# CF_ADC_filter.net
KiCad netlist of a schematic drawn in Altium Designer
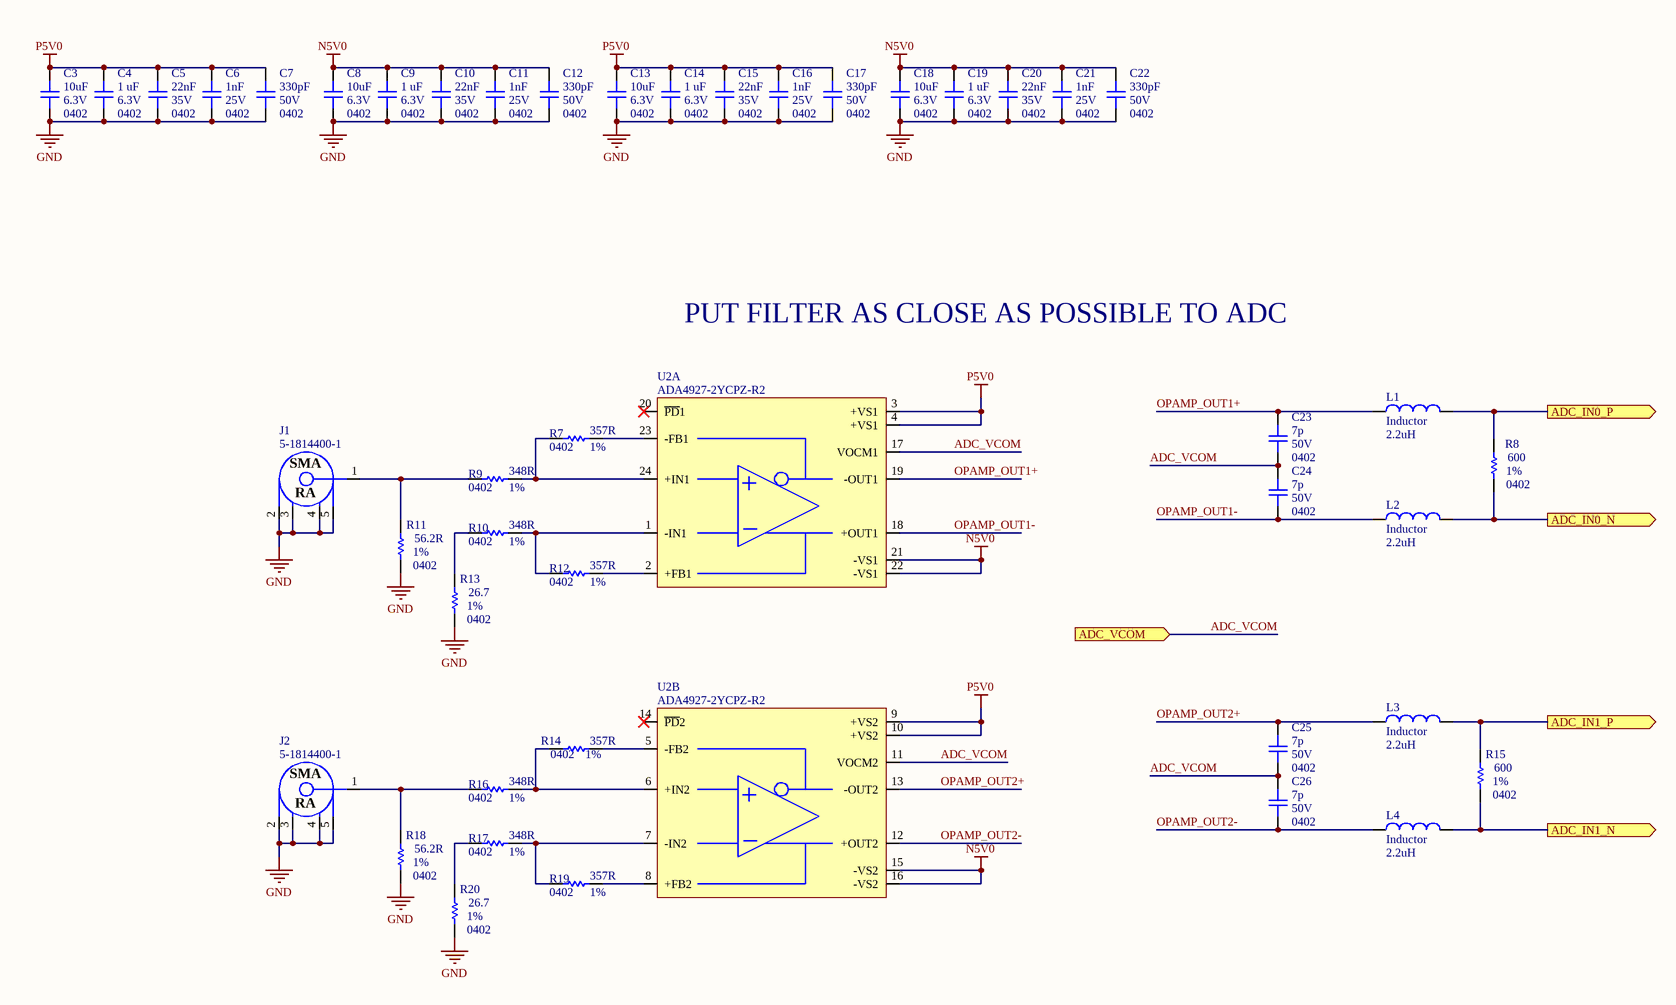
[diagram p0: CF_ADC_filter.SchDoc]

(export (version "E")
  (design (tool "Eeschema 10.0.6"))
  (components
    (comp (ref "C3")
      (value "10uF")
      (footprint "CAP_0402")
      (description "CAP - 0402")
      (fields
        (field (name "VOLTAGE") "6.3V")
        (field (name "PACKAGE") "0402")
        (field (name "CREATEDBY") "Jonathan Bouchard")
      )
      (libsource (lib "S7CAS_Lib2019_REV1_00") (part "CAP - 0402"))
    )
    (comp (ref "C4")
      (value "1 uF")
      (footprint "CAP_0402")
      (description "CAP - 0402")
      (fields
        (field (name "VOLTAGE") "6.3V")
        (field (name "PACKAGE") "0402")
        (field (name "CREATEDBY") "Jonathan Bouchard")
      )
      (libsource (lib "S7CAS_Lib2019_REV1_00") (part "CAP - 0402"))
    )
    (comp (ref "C5")
      (value "22nF")
      (footprint "CAP_0402")
      (description "CAP - 0402")
      (fields
        (field (name "VOLTAGE") "35V")
        (field (name "PACKAGE") "0402")
        (field (name "CREATEDBY") "Jonathan Bouchard")
      )
      (libsource (lib "S7CAS_Lib2019_REV1_00") (part "CAP - 0402"))
    )
    (comp (ref "C6")
      (value "1nF")
      (footprint "CAP_0402")
      (description "CAP - 0402")
      (fields
        (field (name "VOLTAGE") "25V")
        (field (name "PACKAGE") "0402")
        (field (name "CREATEDBY") "Jonathan Bouchard")
      )
      (libsource (lib "S7CAS_Lib2019_REV1_00") (part "CAP - 0402"))
    )
    (comp (ref "C7")
      (value "330pF")
      (footprint "CAP_0402")
      (description "CAP - 0402")
      (fields
        (field (name "VOLTAGE") "50V")
        (field (name "PACKAGE") "0402")
        (field (name "CREATEDBY") "Jonathan Bouchard")
      )
      (libsource (lib "S7CAS_Lib2019_REV1_00") (part "CAP - 0402"))
    )
    (comp (ref "C8")
      (value "10uF")
      (footprint "CAP_0402")
      (description "CAP - 0402")
      (fields
        (field (name "VOLTAGE") "6.3V")
        (field (name "PACKAGE") "0402")
        (field (name "CREATEDBY") "Jonathan Bouchard")
      )
      (libsource (lib "S7CAS_Lib2019_REV1_00") (part "CAP - 0402"))
    )
    (comp (ref "C9")
      (value "1 uF")
      (footprint "CAP_0402")
      (description "CAP - 0402")
      (fields
        (field (name "VOLTAGE") "6.3V")
        (field (name "PACKAGE") "0402")
        (field (name "CREATEDBY") "Jonathan Bouchard")
      )
      (libsource (lib "S7CAS_Lib2019_REV1_00") (part "CAP - 0402"))
    )
    (comp (ref "C10")
      (value "22nF")
      (footprint "CAP_0402")
      (description "CAP - 0402")
      (fields
        (field (name "VOLTAGE") "35V")
        (field (name "PACKAGE") "0402")
        (field (name "CREATEDBY") "Jonathan Bouchard")
      )
      (libsource (lib "S7CAS_Lib2019_REV1_00") (part "CAP - 0402"))
    )
    (comp (ref "C11")
      (value "1nF")
      (footprint "CAP_0402")
      (description "CAP - 0402")
      (fields
        (field (name "VOLTAGE") "25V")
        (field (name "PACKAGE") "0402")
        (field (name "CREATEDBY") "Jonathan Bouchard")
      )
      (libsource (lib "S7CAS_Lib2019_REV1_00") (part "CAP - 0402"))
    )
    (comp (ref "C12")
      (value "330pF")
      (footprint "CAP_0402")
      (description "CAP - 0402")
      (fields
        (field (name "VOLTAGE") "50V")
        (field (name "PACKAGE") "0402")
        (field (name "CREATEDBY") "Jonathan Bouchard")
      )
      (libsource (lib "S7CAS_Lib2019_REV1_00") (part "CAP - 0402"))
    )
    (comp (ref "C13")
      (value "10uF")
      (footprint "CAP_0402")
      (description "CAP - 0402")
      (fields
        (field (name "VOLTAGE") "6.3V")
        (field (name "PACKAGE") "0402")
        (field (name "CREATEDBY") "Jonathan Bouchard")
      )
      (libsource (lib "S7CAS_Lib2019_REV1_00") (part "CAP - 0402"))
    )
    (comp (ref "C14")
      (value "1 uF")
      (footprint "CAP_0402")
      (description "CAP - 0402")
      (fields
        (field (name "VOLTAGE") "6.3V")
        (field (name "PACKAGE") "0402")
        (field (name "CREATEDBY") "Jonathan Bouchard")
      )
      (libsource (lib "S7CAS_Lib2019_REV1_00") (part "CAP - 0402"))
    )
    (comp (ref "C15")
      (value "22nF")
      (footprint "CAP_0402")
      (description "CAP - 0402")
      (fields
        (field (name "VOLTAGE") "35V")
        (field (name "PACKAGE") "0402")
        (field (name "CREATEDBY") "Jonathan Bouchard")
      )
      (libsource (lib "S7CAS_Lib2019_REV1_00") (part "CAP - 0402"))
    )
    (comp (ref "C16")
      (value "1nF")
      (footprint "CAP_0402")
      (description "CAP - 0402")
      (fields
        (field (name "VOLTAGE") "25V")
        (field (name "PACKAGE") "0402")
        (field (name "CREATEDBY") "Jonathan Bouchard")
      )
      (libsource (lib "S7CAS_Lib2019_REV1_00") (part "CAP - 0402"))
    )
    (comp (ref "C17")
      (value "330pF")
      (footprint "CAP_0402")
      (description "CAP - 0402")
      (fields
        (field (name "VOLTAGE") "50V")
        (field (name "PACKAGE") "0402")
        (field (name "CREATEDBY") "Jonathan Bouchard")
      )
      (libsource (lib "S7CAS_Lib2019_REV1_00") (part "CAP - 0402"))
    )
    (comp (ref "C18")
      (value "10uF")
      (footprint "CAP_0402")
      (description "CAP - 0402")
      (fields
        (field (name "VOLTAGE") "6.3V")
        (field (name "PACKAGE") "0402")
        (field (name "CREATEDBY") "Jonathan Bouchard")
      )
      (libsource (lib "S7CAS_Lib2019_REV1_00") (part "CAP - 0402"))
    )
    (comp (ref "C19")
      (value "1 uF")
      (footprint "CAP_0402")
      (description "CAP - 0402")
      (fields
        (field (name "VOLTAGE") "6.3V")
        (field (name "PACKAGE") "0402")
        (field (name "CREATEDBY") "Jonathan Bouchard")
      )
      (libsource (lib "S7CAS_Lib2019_REV1_00") (part "CAP - 0402"))
    )
    (comp (ref "C20")
      (value "22nF")
      (footprint "CAP_0402")
      (description "CAP - 0402")
      (fields
        (field (name "VOLTAGE") "35V")
        (field (name "PACKAGE") "0402")
        (field (name "CREATEDBY") "Jonathan Bouchard")
      )
      (libsource (lib "S7CAS_Lib2019_REV1_00") (part "CAP - 0402"))
    )
    (comp (ref "C21")
      (value "1nF")
      (footprint "CAP_0402")
      (description "CAP - 0402")
      (fields
        (field (name "VOLTAGE") "25V")
        (field (name "PACKAGE") "0402")
        (field (name "CREATEDBY") "Jonathan Bouchard")
      )
      (libsource (lib "S7CAS_Lib2019_REV1_00") (part "CAP - 0402"))
    )
    (comp (ref "C22")
      (value "330pF")
      (footprint "CAP_0402")
      (description "CAP - 0402")
      (fields
        (field (name "VOLTAGE") "50V")
        (field (name "PACKAGE") "0402")
        (field (name "CREATEDBY") "Jonathan Bouchard")
      )
      (libsource (lib "S7CAS_Lib2019_REV1_00") (part "CAP - 0402"))
    )
    (comp (ref "C23")
      (value "7p")
      (footprint "CAP_0402")
      (description "CAP - 0402")
      (fields
        (field (name "VOLTAGE") "50V")
        (field (name "PACKAGE") "0402")
        (field (name "CREATEDBY") "Jonathan Bouchard")
      )
      (libsource (lib "S7CAS_Lib2019_REV1_00") (part "CAP - 0402"))
    )
    (comp (ref "C24")
      (value "7p")
      (footprint "CAP_0402")
      (description "CAP - 0402")
      (fields
        (field (name "VOLTAGE") "50V")
        (field (name "PACKAGE") "0402")
        (field (name "CREATEDBY") "Jonathan Bouchard")
      )
      (libsource (lib "S7CAS_Lib2019_REV1_00") (part "CAP - 0402"))
    )
    (comp (ref "C25")
      (value "7p")
      (footprint "CAP_0402")
      (description "CAP - 0402")
      (fields
        (field (name "VOLTAGE") "50V")
        (field (name "PACKAGE") "0402")
        (field (name "CREATEDBY") "Jonathan Bouchard")
      )
      (libsource (lib "S7CAS_Lib2019_REV1_00") (part "CAP - 0402"))
    )
    (comp (ref "C26")
      (value "7p")
      (footprint "CAP_0402")
      (description "CAP - 0402")
      (fields
        (field (name "VOLTAGE") "50V")
        (field (name "PACKAGE") "0402")
        (field (name "CREATEDBY") "Jonathan Bouchard")
      )
      (libsource (lib "S7CAS_Lib2019_REV1_00") (part "CAP - 0402"))
    )
    (comp (ref "J1")
      (value "5-1814400-1")
      (footprint "CONN_SMA_5-1814400-1")
      (description "CONN -  SMA JACK R/A 50 OHM - TH")
      (fields
        (field (name "MFG") "TE Connectivity AMP Connectors")
        (field (name "CREATEDBY") "Jonathan Bouchard")
      )
      (libsource (lib "S7CAS_Lib2019_REV1_00") (part "CONN_SMA_5-1814400-1"))
    )
    (comp (ref "J2")
      (value "5-1814400-1")
      (footprint "CONN_SMA_5-1814400-1")
      (description "CONN -  SMA JACK R/A 50 OHM - TH")
      (fields
        (field (name "MFG") "TE Connectivity AMP Connectors")
        (field (name "CREATEDBY") "Jonathan Bouchard")
      )
      (libsource (lib "S7CAS_Lib2019_REV1_00") (part "CONN_SMA_5-1814400-1"))
    )
    (comp (ref "L1")
      (value "Inductor")
      (footprint "0402-A")
      (fields (field (name "ALTIUM_VALUE") "2.2uH") (field (name "PUBLISHER") "Altium Limited"))
      (libsource (lib "Miscellaneous Devices") (part "Inductor"))
    )
    (comp (ref "L2")
      (value "Inductor")
      (footprint "0402-A")
      (fields (field (name "ALTIUM_VALUE") "2.2uH") (field (name "PUBLISHER") "Altium Limited"))
      (libsource (lib "Miscellaneous Devices") (part "Inductor"))
    )
    (comp (ref "L3")
      (value "Inductor")
      (footprint "0402-A")
      (fields (field (name "ALTIUM_VALUE") "2.2uH") (field (name "PUBLISHER") "Altium Limited"))
      (libsource (lib "Miscellaneous Devices") (part "Inductor"))
    )
    (comp (ref "L4")
      (value "Inductor")
      (footprint "0402-A")
      (fields (field (name "ALTIUM_VALUE") "2.2uH") (field (name "PUBLISHER") "Altium Limited"))
      (libsource (lib "Miscellaneous Devices") (part "Inductor"))
    )
    (comp (ref "R7")
      (value "357R")
      (footprint "RES_0402")
      (description "RES - 0402")
      (fields
        (field (name "VOLTAGE") "50V")
        (field (name "POWER") "1/16W")
        (field (name "PACKAGE") "0402")
        (field (name "PRECISION") "1%")
        (field (name "CREATEDBY") "Jonathan Bouchard")
      )
      (libsource (lib "S7CAS_Lib2019_REV1_00") (part "RES - 0402"))
    )
    (comp (ref "R8")
      (value "600")
      (footprint "RES_0402")
      (description "RES - 0402")
      (fields
        (field (name "VOLTAGE") "50V")
        (field (name "POWER") "1/16W")
        (field (name "PACKAGE") "0402")
        (field (name "PRECISION") "1%")
        (field (name "CREATEDBY") "Jonathan Bouchard")
      )
      (libsource (lib "S7CAS_Lib2019_REV1_00") (part "RES - 0402"))
    )
    (comp (ref "R9")
      (value "348R")
      (footprint "RES_0402")
      (description "RES - 0402")
      (fields
        (field (name "VOLTAGE") "50V")
        (field (name "POWER") "1/16W")
        (field (name "PACKAGE") "0402")
        (field (name "PRECISION") "1%")
        (field (name "CREATEDBY") "Jonathan Bouchard")
      )
      (libsource (lib "S7CAS_Lib2019_REV1_00") (part "RES - 0402"))
    )
    (comp (ref "R10")
      (value "348R")
      (footprint "RES_0402")
      (description "RES - 0402")
      (fields
        (field (name "VOLTAGE") "50V")
        (field (name "POWER") "1/16W")
        (field (name "PACKAGE") "0402")
        (field (name "PRECISION") "1%")
        (field (name "CREATEDBY") "Jonathan Bouchard")
      )
      (libsource (lib "S7CAS_Lib2019_REV1_00") (part "RES - 0402"))
    )
    (comp (ref "R11")
      (value "56.2R")
      (footprint "RES_0402")
      (description "RES - 0402")
      (fields
        (field (name "VOLTAGE") "50V")
        (field (name "POWER") "1/16W")
        (field (name "PACKAGE") "0402")
        (field (name "PRECISION") "1%")
        (field (name "CREATEDBY") "Jonathan Bouchard")
      )
      (libsource (lib "S7CAS_Lib2019_REV1_00") (part "RES - 0402"))
    )
    (comp (ref "R12")
      (value "357R")
      (footprint "RES_0402")
      (description "RES - 0402")
      (fields
        (field (name "VOLTAGE") "50V")
        (field (name "POWER") "1/16W")
        (field (name "PACKAGE") "0402")
        (field (name "PRECISION") "1%")
        (field (name "CREATEDBY") "Jonathan Bouchard")
      )
      (libsource (lib "S7CAS_Lib2019_REV1_00") (part "RES - 0402"))
    )
    (comp (ref "R13")
      (value "26.7")
      (footprint "RES_0402")
      (description "RES - 0402")
      (fields
        (field (name "VOLTAGE") "50V")
        (field (name "POWER") "1/16W")
        (field (name "PACKAGE") "0402")
        (field (name "PRECISION") "1%")
        (field (name "CREATEDBY") "Jonathan Bouchard")
      )
      (libsource (lib "S7CAS_Lib2019_REV1_00") (part "RES - 0402"))
    )
    (comp (ref "R14")
      (value "357R")
      (footprint "RES_0402")
      (description "RES - 0402")
      (fields
        (field (name "VOLTAGE") "50V")
        (field (name "POWER") "1/16W")
        (field (name "PACKAGE") "0402")
        (field (name "PRECISION") "1%")
        (field (name "CREATEDBY") "Jonathan Bouchard")
      )
      (libsource (lib "S7CAS_Lib2019_REV1_00") (part "RES - 0402"))
    )
    (comp (ref "R15")
      (value "600")
      (footprint "RES_0402")
      (description "RES - 0402")
      (fields
        (field (name "VOLTAGE") "50V")
        (field (name "POWER") "1/16W")
        (field (name "PACKAGE") "0402")
        (field (name "PRECISION") "1%")
        (field (name "CREATEDBY") "Jonathan Bouchard")
      )
      (libsource (lib "S7CAS_Lib2019_REV1_00") (part "RES - 0402"))
    )
    (comp (ref "R16")
      (value "348R")
      (footprint "RES_0402")
      (description "RES - 0402")
      (fields
        (field (name "VOLTAGE") "50V")
        (field (name "POWER") "1/16W")
        (field (name "PACKAGE") "0402")
        (field (name "PRECISION") "1%")
        (field (name "CREATEDBY") "Jonathan Bouchard")
      )
      (libsource (lib "S7CAS_Lib2019_REV1_00") (part "RES - 0402"))
    )
    (comp (ref "R17")
      (value "348R")
      (footprint "RES_0402")
      (description "RES - 0402")
      (fields
        (field (name "VOLTAGE") "50V")
        (field (name "POWER") "1/16W")
        (field (name "PACKAGE") "0402")
        (field (name "PRECISION") "1%")
        (field (name "CREATEDBY") "Jonathan Bouchard")
      )
      (libsource (lib "S7CAS_Lib2019_REV1_00") (part "RES - 0402"))
    )
    (comp (ref "R18")
      (value "56.2R")
      (footprint "RES_0402")
      (description "RES - 0402")
      (fields
        (field (name "VOLTAGE") "50V")
        (field (name "POWER") "1/16W")
        (field (name "PACKAGE") "0402")
        (field (name "PRECISION") "1%")
        (field (name "CREATEDBY") "Jonathan Bouchard")
      )
      (libsource (lib "S7CAS_Lib2019_REV1_00") (part "RES - 0402"))
    )
    (comp (ref "R19")
      (value "357R")
      (footprint "RES_0402")
      (description "RES - 0402")
      (fields
        (field (name "VOLTAGE") "50V")
        (field (name "POWER") "1/16W")
        (field (name "PACKAGE") "0402")
        (field (name "PRECISION") "1%")
        (field (name "CREATEDBY") "Jonathan Bouchard")
      )
      (libsource (lib "S7CAS_Lib2019_REV1_00") (part "RES - 0402"))
    )
    (comp (ref "R20")
      (value "26.7")
      (footprint "RES_0402")
      (description "RES - 0402")
      (fields
        (field (name "VOLTAGE") "50V")
        (field (name "POWER") "1/16W")
        (field (name "PACKAGE") "0402")
        (field (name "PRECISION") "1%")
        (field (name "CREATEDBY") "Jonathan Bouchard")
      )
      (libsource (lib "S7CAS_Lib2019_REV1_00") (part "RES - 0402"))
    )
    (comp (ref "U2")
      (value "ADA4927-2YCPZ-R2")
      (footprint "OPAMP_ADA4927-2YCPZ-R2")
      (description "OPAMP - CFA 2.3GHZ - QFN-24")
      (fields
        (field (name "VOLTAGE") "4.5 V ~ 11 V, ±2.25 V ~ 5.5 V")
        (field (name "MFG") "Analog Devices")
        (field (name "CREATEDBY") "Jonathan Bouchard")
      )
      (libsource (lib "S7CAS_Lib2019_REV1_00") (part "OPAMP_ADA4927-2YCPZ-R2"))
    )
  )
  (nets
    (net (code "1") (name "/ADC_IN0_N") (class "Default")
      (node (ref "L2") (pin "2") (pinfunction "2_2") (pintype "passive"))
      (node (ref "R8") (pin "1") (pinfunction "1_1") (pintype "passive"))
    )
    (net (code "2") (name "/ADC_IN0_P") (class "Default")
      (node (ref "L1") (pin "2") (pinfunction "2_2") (pintype "passive"))
      (node (ref "R8") (pin "2") (pinfunction "2_2") (pintype "passive"))
    )
    (net (code "3") (name "/ADC_IN1_N") (class "Default")
      (node (ref "L4") (pin "2") (pinfunction "2_2") (pintype "passive"))
      (node (ref "R15") (pin "1") (pinfunction "1_1") (pintype "passive"))
    )
    (net (code "4") (name "/ADC_IN1_P") (class "Default")
      (node (ref "L3") (pin "2") (pinfunction "2_2") (pintype "passive"))
      (node (ref "R15") (pin "2") (pinfunction "2_2") (pintype "passive"))
    )
    (net (code "5") (name "/ADC_VCOM") (class "Default")
      (node (ref "C23") (pin "1") (pinfunction "1_1") (pintype "passive"))
      (node (ref "C24") (pin "2") (pinfunction "2_2") (pintype "passive"))
      (node (ref "C25") (pin "1") (pinfunction "1_1") (pintype "passive"))
      (node (ref "C26") (pin "2") (pinfunction "2_2") (pintype "passive"))
      (node (ref "U2") (pin "11") (pinfunction "VOCM2_11") (pintype "passive"))
      (node (ref "U2") (pin "17") (pinfunction "VOCM1_17") (pintype "passive"))
    )
    (net (code "6") (name "/OPAMP_OUT1+") (class "Default")
      (node (ref "C23") (pin "2") (pinfunction "2_2") (pintype "passive"))
      (node (ref "L1") (pin "1") (pinfunction "1_1") (pintype "passive"))
      (node (ref "U2") (pin "19") (pinfunction "-OUT1_19") (pintype "passive"))
    )
    (net (code "7") (name "/OPAMP_OUT1-") (class "Default")
      (node (ref "C24") (pin "1") (pinfunction "1_1") (pintype "passive"))
      (node (ref "L2") (pin "1") (pinfunction "1_1") (pintype "passive"))
      (node (ref "U2") (pin "18") (pinfunction "+OUT1_18") (pintype "passive"))
    )
    (net (code "8") (name "/OPAMP_OUT2+") (class "Default")
      (node (ref "C25") (pin "2") (pinfunction "2_2") (pintype "passive"))
      (node (ref "L3") (pin "1") (pinfunction "1_1") (pintype "passive"))
      (node (ref "U2") (pin "13") (pinfunction "-OUT2_13") (pintype "passive"))
    )
    (net (code "9") (name "/OPAMP_OUT2-") (class "Default")
      (node (ref "C26") (pin "1") (pinfunction "1_1") (pintype "passive"))
      (node (ref "L4") (pin "1") (pinfunction "1_1") (pintype "passive"))
      (node (ref "U2") (pin "12") (pinfunction "+OUT2_12") (pintype "passive"))
    )
    (net (code "10") (name "GND") (class "Default")
      (node (ref "C10") (pin "1") (pinfunction "1_1") (pintype "passive"))
      (node (ref "C11") (pin "1") (pinfunction "1_1") (pintype "passive"))
      (node (ref "C12") (pin "1") (pinfunction "1_1") (pintype "passive"))
      (node (ref "C13") (pin "1") (pinfunction "1_1") (pintype "passive"))
      (node (ref "C14") (pin "1") (pinfunction "1_1") (pintype "passive"))
      (node (ref "C15") (pin "1") (pinfunction "1_1") (pintype "passive"))
      (node (ref "C16") (pin "1") (pinfunction "1_1") (pintype "passive"))
      (node (ref "C17") (pin "1") (pinfunction "1_1") (pintype "passive"))
      (node (ref "C18") (pin "1") (pinfunction "1_1") (pintype "passive"))
      (node (ref "C19") (pin "1") (pinfunction "1_1") (pintype "passive"))
      (node (ref "C20") (pin "1") (pinfunction "1_1") (pintype "passive"))
      (node (ref "C21") (pin "1") (pinfunction "1_1") (pintype "passive"))
      (node (ref "C22") (pin "1") (pinfunction "1_1") (pintype "passive"))
      (node (ref "C3") (pin "1") (pinfunction "1_1") (pintype "passive"))
      (node (ref "C4") (pin "1") (pinfunction "1_1") (pintype "passive"))
      (node (ref "C5") (pin "1") (pinfunction "1_1") (pintype "passive"))
      (node (ref "C6") (pin "1") (pinfunction "1_1") (pintype "passive"))
      (node (ref "C7") (pin "1") (pinfunction "1_1") (pintype "passive"))
      (node (ref "C8") (pin "1") (pinfunction "1_1") (pintype "passive"))
      (node (ref "C9") (pin "1") (pinfunction "1_1") (pintype "passive"))
      (node (ref "J1") (pin "2") (pinfunction "2_2") (pintype "passive"))
      (node (ref "J1") (pin "3") (pinfunction "3_3") (pintype "passive"))
      (node (ref "J1") (pin "4") (pinfunction "4_4") (pintype "passive"))
      (node (ref "J1") (pin "5") (pinfunction "5_5") (pintype "passive"))
      (node (ref "J2") (pin "2") (pinfunction "2_2") (pintype "passive"))
      (node (ref "J2") (pin "3") (pinfunction "3_3") (pintype "passive"))
      (node (ref "J2") (pin "4") (pinfunction "4_4") (pintype "passive"))
      (node (ref "J2") (pin "5") (pinfunction "5_5") (pintype "passive"))
      (node (ref "R11") (pin "1") (pinfunction "1_1") (pintype "passive"))
      (node (ref "R13") (pin "1") (pinfunction "1_1") (pintype "passive"))
      (node (ref "R18") (pin "1") (pinfunction "1_1") (pintype "passive"))
      (node (ref "R20") (pin "1") (pinfunction "1_1") (pintype "passive"))
    )
    (net (code "11") (name "N5V0") (class "Default")
      (node (ref "C10") (pin "2") (pinfunction "2_2") (pintype "passive"))
      (node (ref "C11") (pin "2") (pinfunction "2_2") (pintype "passive"))
      (node (ref "C12") (pin "2") (pinfunction "2_2") (pintype "passive"))
      (node (ref "C18") (pin "2") (pinfunction "2_2") (pintype "passive"))
      (node (ref "C19") (pin "2") (pinfunction "2_2") (pintype "passive"))
      (node (ref "C20") (pin "2") (pinfunction "2_2") (pintype "passive"))
      (node (ref "C21") (pin "2") (pinfunction "2_2") (pintype "passive"))
      (node (ref "C22") (pin "2") (pinfunction "2_2") (pintype "passive"))
      (node (ref "C8") (pin "2") (pinfunction "2_2") (pintype "passive"))
      (node (ref "C9") (pin "2") (pinfunction "2_2") (pintype "passive"))
      (node (ref "U2") (pin "15") (pinfunction "-VS2_15") (pintype "passive"))
      (node (ref "U2") (pin "16") (pinfunction "-VS2_16") (pintype "passive"))
      (node (ref "U2") (pin "21") (pinfunction "-VS1_21") (pintype "passive"))
      (node (ref "U2") (pin "22") (pinfunction "-VS1_22") (pintype "passive"))
    )
    (net (code "12") (name "Net-(J1-Pad1)") (class "Default")
      (node (ref "J1") (pin "1") (pinfunction "1_1") (pintype "passive"))
      (node (ref "R11") (pin "2") (pinfunction "2_2") (pintype "passive"))
      (node (ref "R9") (pin "2") (pinfunction "2_2") (pintype "passive"))
    )
    (net (code "13") (name "Net-(J2-Pad1)") (class "Default")
      (node (ref "J2") (pin "1") (pinfunction "1_1") (pintype "passive"))
      (node (ref "R16") (pin "2") (pinfunction "2_2") (pintype "passive"))
      (node (ref "R18") (pin "2") (pinfunction "2_2") (pintype "passive"))
    )
    (net (code "14") (name "Net-(R10-Pad2)") (class "Default")
      (node (ref "R10") (pin "2") (pinfunction "2_2") (pintype "passive"))
      (node (ref "R13") (pin "2") (pinfunction "2_2") (pintype "passive"))
    )
    (net (code "15") (name "Net-(R17-Pad2)") (class "Default")
      (node (ref "R17") (pin "2") (pinfunction "2_2") (pintype "passive"))
      (node (ref "R20") (pin "2") (pinfunction "2_2") (pintype "passive"))
    )
    (net (code "16") (name "Net-(U2A-+FB1)") (class "Default")
      (node (ref "R12") (pin "1") (pinfunction "1_1") (pintype "passive"))
      (node (ref "U2") (pin "2") (pinfunction "+FB1_2") (pintype "passive"))
    )
    (net (code "17") (name "Net-(U2A-+IN1)") (class "Default")
      (node (ref "R7") (pin "2") (pinfunction "2_2") (pintype "passive"))
      (node (ref "R9") (pin "1") (pinfunction "1_1") (pintype "passive"))
      (node (ref "U2") (pin "24") (pinfunction "+IN1_24") (pintype "passive"))
    )
    (net (code "18") (name "Net-(U2A--FB1)") (class "Default")
      (node (ref "R7") (pin "1") (pinfunction "1_1") (pintype "passive"))
      (node (ref "U2") (pin "23") (pinfunction "-FB1_23") (pintype "passive"))
    )
    (net (code "19") (name "Net-(U2A--IN1)") (class "Default")
      (node (ref "R10") (pin "1") (pinfunction "1_1") (pintype "passive"))
      (node (ref "R12") (pin "2") (pinfunction "2_2") (pintype "passive"))
      (node (ref "U2") (pin "1") (pinfunction "-IN1_1") (pintype "passive"))
    )
    (net (code "20") (name "Net-(U2B-+FB2)") (class "Default")
      (node (ref "R19") (pin "1") (pinfunction "1_1") (pintype "passive"))
      (node (ref "U2") (pin "8") (pinfunction "+FB2_8") (pintype "passive"))
    )
    (net (code "21") (name "Net-(U2B-+IN2)") (class "Default")
      (node (ref "R14") (pin "2") (pinfunction "2_2") (pintype "passive"))
      (node (ref "R16") (pin "1") (pinfunction "1_1") (pintype "passive"))
      (node (ref "U2") (pin "6") (pinfunction "+IN2_6") (pintype "passive"))
    )
    (net (code "22") (name "Net-(U2B--FB2)") (class "Default")
      (node (ref "R14") (pin "1") (pinfunction "1_1") (pintype "passive"))
      (node (ref "U2") (pin "5") (pinfunction "-FB2_5") (pintype "passive"))
    )
    (net (code "23") (name "Net-(U2B--IN2)") (class "Default")
      (node (ref "R17") (pin "1") (pinfunction "1_1") (pintype "passive"))
      (node (ref "R19") (pin "2") (pinfunction "2_2") (pintype "passive"))
      (node (ref "U2") (pin "7") (pinfunction "-IN2_7") (pintype "passive"))
    )
    (net (code "24") (name "P5V0") (class "Default")
      (node (ref "C13") (pin "2") (pinfunction "2_2") (pintype "passive"))
      (node (ref "C14") (pin "2") (pinfunction "2_2") (pintype "passive"))
      (node (ref "C15") (pin "2") (pinfunction "2_2") (pintype "passive"))
      (node (ref "C16") (pin "2") (pinfunction "2_2") (pintype "passive"))
      (node (ref "C17") (pin "2") (pinfunction "2_2") (pintype "passive"))
      (node (ref "C3") (pin "2") (pinfunction "2_2") (pintype "passive"))
      (node (ref "C4") (pin "2") (pinfunction "2_2") (pintype "passive"))
      (node (ref "C5") (pin "2") (pinfunction "2_2") (pintype "passive"))
      (node (ref "C6") (pin "2") (pinfunction "2_2") (pintype "passive"))
      (node (ref "C7") (pin "2") (pinfunction "2_2") (pintype "passive"))
      (node (ref "U2") (pin "10") (pinfunction "+VS2_10") (pintype "passive"))
      (node (ref "U2") (pin "3") (pinfunction "+VS1_3") (pintype "passive"))
      (node (ref "U2") (pin "4") (pinfunction "+VS1_4") (pintype "passive"))
      (node (ref "U2") (pin "9") (pinfunction "+VS2_9") (pintype "passive"))
    )
    (net (code "25") (name "unconnected-(U2A-~{PD}1-Pad20)") (class "Default")
      (node (ref "U2") (pin "20") (pinfunction "~{PD}1_20") (pintype "passive+no_connect"))
    )
    (net (code "26") (name "unconnected-(U2B-~{PD}2-Pad14)") (class "Default")
      (node (ref "U2") (pin "14") (pinfunction "~{PD}2_14") (pintype "passive+no_connect"))
    )
  )
)
